# HackflightBrushed.net
KiCad netlist of a schematic drawn in EAGLE
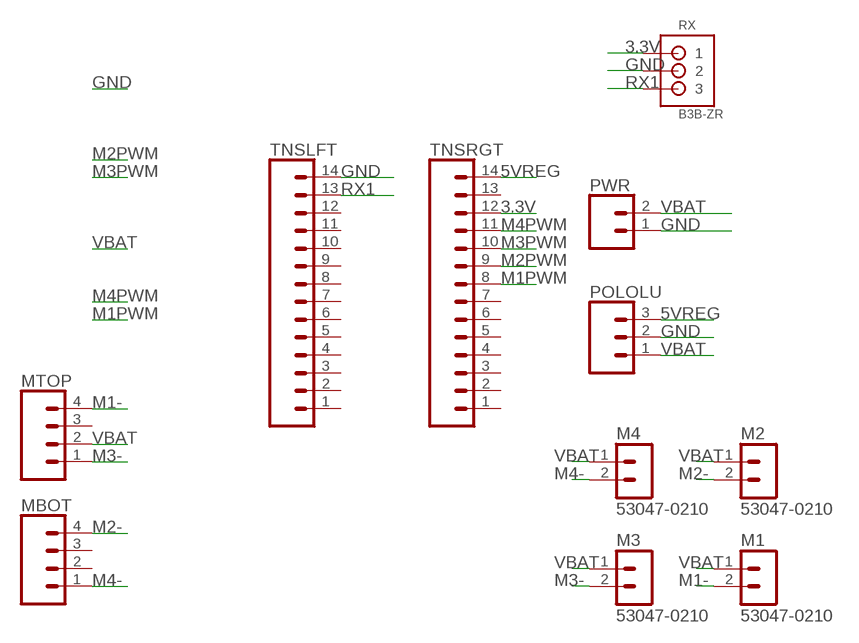
[diagram p0: schematic, sheet 1]

(export (version "E")
  (design (tool "Eeschema 10.0.6"))
  (components
    (comp (ref "M1")
      (value "53047-0210")
      (footprint "eagle-import:53047-0210")
      (libsource (lib "eagle-import") (part "53047-0210"))
    )
    (comp (ref "M2")
      (value "53047-0210")
      (footprint "eagle-import:53047-0210")
      (libsource (lib "eagle-import") (part "53047-0210"))
    )
    (comp (ref "M3")
      (value "53047-0210")
      (footprint "eagle-import:53047-0210")
      (libsource (lib "eagle-import") (part "53047-0210"))
    )
    (comp (ref "M4")
      (value "53047-0210")
      (footprint "eagle-import:53047-0210")
      (libsource (lib "eagle-import") (part "53047-0210"))
    )
    (comp (ref "MBOT")
      (value "CONN_04")
      (footprint "eagle-import:1X04")
      (libsource (lib "eagle-import") (part "CONN_04"))
    )
    (comp (ref "MTOP")
      (value "CONN_04")
      (footprint "eagle-import:1X04")
      (libsource (lib "eagle-import") (part "CONN_04"))
    )
    (comp (ref "POLOLU")
      (value "CONN_03")
      (footprint "eagle-import:1X03")
      (libsource (lib "eagle-import") (part "CONN_03"))
    )
    (comp (ref "PWR")
      (value "CONN_02")
      (footprint "eagle-import:1X02")
      (libsource (lib "eagle-import") (part "CONN_02"))
    )
    (comp (ref "RX")
      (value "B3B-ZR")
      (footprint "eagle-import:B3B-ZR")
      (libsource (lib "eagle-import") (part "B3B-ZR"))
    )
    (comp (ref "TNSLFT")
      (value "CONN_14")
      (footprint "eagle-import:1X14")
      (libsource (lib "eagle-import") (part "CONN_14"))
    )
    (comp (ref "TNSRGT")
      (value "CONN_14")
      (footprint "eagle-import:1X14")
      (libsource (lib "eagle-import") (part "CONN_14"))
    )
  )
  (nets
    (net (code "1") (name "/3.3V") (class "Default")
      (node (ref "RX") (pin "1") (pinfunction "1_1") (pintype "bidirectional"))
      (node (ref "TNSRGT") (pin "12") (pinfunction "12_12") (pintype "passive"))
    )
    (net (code "2") (name "/5VREG") (class "Default")
      (node (ref "POLOLU") (pin "3") (pinfunction "3_3") (pintype "passive"))
      (node (ref "TNSRGT") (pin "14") (pinfunction "14_14") (pintype "passive"))
    )
    (net (code "3") (name "/GND") (class "Default")
      (node (ref "POLOLU") (pin "2") (pinfunction "2_2") (pintype "passive"))
      (node (ref "PWR") (pin "1") (pinfunction "1_1") (pintype "passive"))
      (node (ref "RX") (pin "2") (pinfunction "2_2") (pintype "bidirectional"))
      (node (ref "TNSLFT") (pin "14") (pinfunction "14_14") (pintype "passive"))
    )
    (net (code "4") (name "/M1-") (class "Default")
      (node (ref "M1") (pin "2") (pinfunction "2_2") (pintype "passive"))
      (node (ref "MTOP") (pin "4") (pinfunction "4_4") (pintype "passive"))
    )
    (net (code "5") (name "/M1PWM") (class "Default")
      (node (ref "TNSRGT") (pin "8") (pinfunction "8_8") (pintype "passive"))
    )
    (net (code "6") (name "/M2-") (class "Default")
      (node (ref "M2") (pin "2") (pinfunction "2_2") (pintype "passive"))
      (node (ref "MBOT") (pin "4") (pinfunction "4_4") (pintype "passive"))
    )
    (net (code "7") (name "/M2PWM") (class "Default")
      (node (ref "TNSRGT") (pin "9") (pinfunction "9_9") (pintype "passive"))
    )
    (net (code "8") (name "/M3-") (class "Default")
      (node (ref "M3") (pin "2") (pinfunction "2_2") (pintype "passive"))
      (node (ref "MTOP") (pin "1") (pinfunction "1_1") (pintype "passive"))
    )
    (net (code "9") (name "/M3PWM") (class "Default")
      (node (ref "TNSRGT") (pin "10") (pinfunction "10_10") (pintype "passive"))
    )
    (net (code "10") (name "/M4-") (class "Default")
      (node (ref "M4") (pin "2") (pinfunction "2_2") (pintype "passive"))
      (node (ref "MBOT") (pin "1") (pinfunction "1_1") (pintype "passive"))
    )
    (net (code "11") (name "/M4PWM") (class "Default")
      (node (ref "TNSRGT") (pin "11") (pinfunction "11_11") (pintype "passive"))
    )
    (net (code "12") (name "/RX1") (class "Default")
      (node (ref "RX") (pin "3") (pinfunction "3_3") (pintype "bidirectional"))
      (node (ref "TNSLFT") (pin "13") (pinfunction "13_13") (pintype "passive"))
    )
    (net (code "13") (name "/VBAT") (class "Default")
      (node (ref "M1") (pin "1") (pinfunction "1_1") (pintype "passive"))
      (node (ref "M2") (pin "1") (pinfunction "1_1") (pintype "passive"))
      (node (ref "M3") (pin "1") (pinfunction "1_1") (pintype "passive"))
      (node (ref "M4") (pin "1") (pinfunction "1_1") (pintype "passive"))
      (node (ref "MTOP") (pin "2") (pinfunction "2_2") (pintype "passive"))
      (node (ref "POLOLU") (pin "1") (pinfunction "1_1") (pintype "passive"))
      (node (ref "PWR") (pin "2") (pinfunction "2_2") (pintype "passive"))
    )
    (net (code "14") (name "unconnected-(MBOT-Pad2)") (class "Default")
      (node (ref "MBOT") (pin "2") (pinfunction "2_2") (pintype "passive"))
    )
    (net (code "15") (name "unconnected-(MBOT-Pad3)") (class "Default")
      (node (ref "MBOT") (pin "3") (pinfunction "3_3") (pintype "passive"))
    )
    (net (code "16") (name "unconnected-(MTOP-Pad3)") (class "Default")
      (node (ref "MTOP") (pin "3") (pinfunction "3_3") (pintype "passive"))
    )
    (net (code "17") (name "unconnected-(TNSLFT-Pad1)") (class "Default")
      (node (ref "TNSLFT") (pin "1") (pinfunction "1_1") (pintype "passive"))
    )
    (net (code "18") (name "unconnected-(TNSLFT-Pad2)") (class "Default")
      (node (ref "TNSLFT") (pin "2") (pinfunction "2_2") (pintype "passive"))
    )
    (net (code "19") (name "unconnected-(TNSLFT-Pad3)") (class "Default")
      (node (ref "TNSLFT") (pin "3") (pinfunction "3_3") (pintype "passive"))
    )
    (net (code "20") (name "unconnected-(TNSLFT-Pad4)") (class "Default")
      (node (ref "TNSLFT") (pin "4") (pinfunction "4_4") (pintype "passive"))
    )
    (net (code "21") (name "unconnected-(TNSLFT-Pad5)") (class "Default")
      (node (ref "TNSLFT") (pin "5") (pinfunction "5_5") (pintype "passive"))
    )
    (net (code "22") (name "unconnected-(TNSLFT-Pad6)") (class "Default")
      (node (ref "TNSLFT") (pin "6") (pinfunction "6_6") (pintype "passive"))
    )
    (net (code "23") (name "unconnected-(TNSLFT-Pad7)") (class "Default")
      (node (ref "TNSLFT") (pin "7") (pinfunction "7_7") (pintype "passive"))
    )
    (net (code "24") (name "unconnected-(TNSLFT-Pad8)") (class "Default")
      (node (ref "TNSLFT") (pin "8") (pinfunction "8_8") (pintype "passive"))
    )
    (net (code "25") (name "unconnected-(TNSLFT-Pad9)") (class "Default")
      (node (ref "TNSLFT") (pin "9") (pinfunction "9_9") (pintype "passive"))
    )
    (net (code "26") (name "unconnected-(TNSLFT-Pad10)") (class "Default")
      (node (ref "TNSLFT") (pin "10") (pinfunction "10_10") (pintype "passive"))
    )
    (net (code "27") (name "unconnected-(TNSLFT-Pad11)") (class "Default")
      (node (ref "TNSLFT") (pin "11") (pinfunction "11_11") (pintype "passive"))
    )
    (net (code "28") (name "unconnected-(TNSLFT-Pad12)") (class "Default")
      (node (ref "TNSLFT") (pin "12") (pinfunction "12_12") (pintype "passive"))
    )
    (net (code "29") (name "unconnected-(TNSRGT-Pad1)") (class "Default")
      (node (ref "TNSRGT") (pin "1") (pinfunction "1_1") (pintype "passive"))
    )
    (net (code "30") (name "unconnected-(TNSRGT-Pad2)") (class "Default")
      (node (ref "TNSRGT") (pin "2") (pinfunction "2_2") (pintype "passive"))
    )
    (net (code "31") (name "unconnected-(TNSRGT-Pad3)") (class "Default")
      (node (ref "TNSRGT") (pin "3") (pinfunction "3_3") (pintype "passive"))
    )
    (net (code "32") (name "unconnected-(TNSRGT-Pad4)") (class "Default")
      (node (ref "TNSRGT") (pin "4") (pinfunction "4_4") (pintype "passive"))
    )
    (net (code "33") (name "unconnected-(TNSRGT-Pad5)") (class "Default")
      (node (ref "TNSRGT") (pin "5") (pinfunction "5_5") (pintype "passive"))
    )
    (net (code "34") (name "unconnected-(TNSRGT-Pad6)") (class "Default")
      (node (ref "TNSRGT") (pin "6") (pinfunction "6_6") (pintype "passive"))
    )
    (net (code "35") (name "unconnected-(TNSRGT-Pad7)") (class "Default")
      (node (ref "TNSRGT") (pin "7") (pinfunction "7_7") (pintype "passive"))
    )
    (net (code "36") (name "unconnected-(TNSRGT-Pad13)") (class "Default")
      (node (ref "TNSRGT") (pin "13") (pinfunction "13_13") (pintype "passive"))
    )
  )
)
